# samplehold.net
KiCad netlist of a schematic drawn in EAGLE
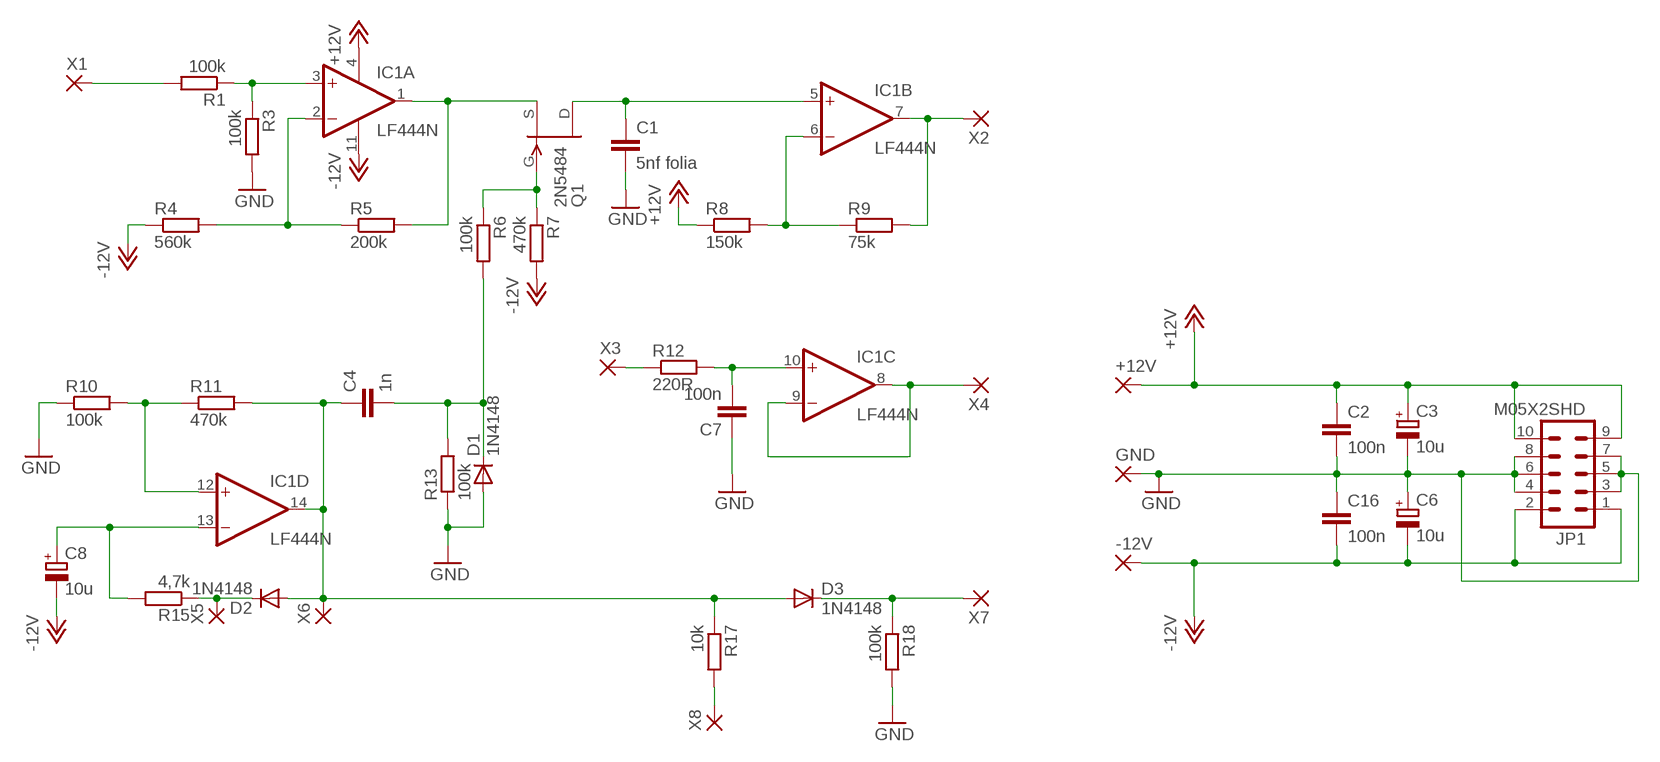
[diagram p0: schematic, sheet 1]
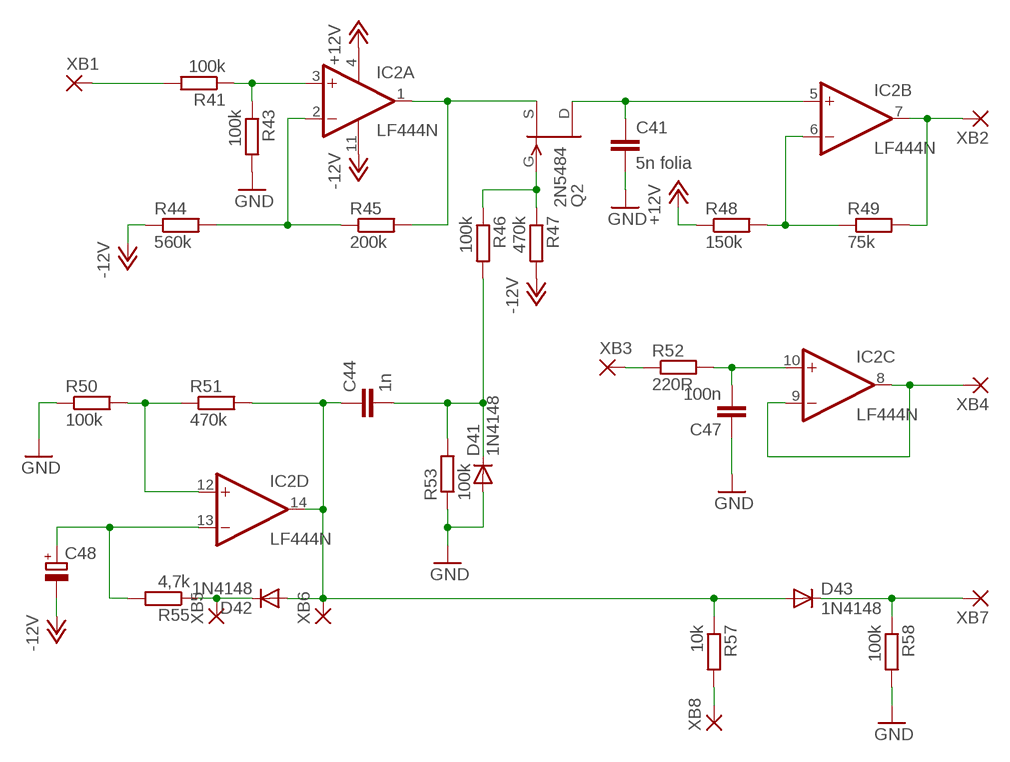
[diagram p1: schematic, sheet 2]

(export (version "E")
  (design (tool "Eeschema 10.0.6"))
  (components
    (comp (ref "+12V")
      (value "2,54/1,0")
      (footprint "eagle-import:2,54_1,0")
      (libsource (lib "eagle-import") (part "2,54/1,0"))
    )
    (comp (ref "-12V")
      (value "2,54/1,0")
      (footprint "eagle-import:2,54_1,0")
      (libsource (lib "eagle-import") (part "2,54/1,0"))
    )
    (comp (ref "C1")
      (value "5nf folia")
      (footprint "eagle-import:C050-035X075")
      (libsource (lib "eagle-import") (part "C-EU050-035X075"))
    )
    (comp (ref "C2")
      (value "100n")
      (footprint "eagle-import:C050-035X075")
      (libsource (lib "eagle-import") (part "C-EU050-035X075"))
    )
    (comp (ref "C3")
      (value "10u")
      (footprint "eagle-import:E3,5-8")
      (libsource (lib "eagle-import") (part "CPOL-EUE3.5-8"))
    )
    (comp (ref "C4")
      (value "1n")
      (footprint "eagle-import:C050-035X075")
      (libsource (lib "eagle-import") (part "C-EU050-035X075"))
    )
    (comp (ref "C6")
      (value "10u")
      (footprint "eagle-import:E3,5-8")
      (libsource (lib "eagle-import") (part "CPOL-EUE3.5-8"))
    )
    (comp (ref "C7")
      (value "100n")
      (footprint "eagle-import:C050-035X075")
      (libsource (lib "eagle-import") (part "C-EU050-035X075"))
    )
    (comp (ref "C8")
      (value "10u")
      (footprint "eagle-import:E2,5-7")
      (libsource (lib "eagle-import") (part "CPOL-EUE2.5-7"))
    )
    (comp (ref "C16")
      (value "100n")
      (footprint "eagle-import:C050-035X075")
      (libsource (lib "eagle-import") (part "C-EU050-035X075"))
    )
    (comp (ref "D1")
      (value "1N4148")
      (footprint "eagle-import:DO35-7")
      (libsource (lib "eagle-import") (part "1N4148DO35-7"))
    )
    (comp (ref "D2")
      (value "1N4148")
      (footprint "eagle-import:DO35-7")
      (libsource (lib "eagle-import") (part "1N4148DO35-7"))
    )
    (comp (ref "D3")
      (value "1N4148")
      (footprint "eagle-import:DO35-7")
      (libsource (lib "eagle-import") (part "1N4148DO35-7"))
    )
    (comp (ref "GND")
      (value "2,54/1,0")
      (footprint "eagle-import:2,54_1,0")
      (libsource (lib "eagle-import") (part "2,54/1,0"))
    )
    (comp (ref "IC1")
      (value "LF444N")
      (footprint "eagle-import:DIL14")
      (libsource (lib "eagle-import") (part "LF444N"))
    )
    (comp (ref "JP1")
      (value "M05X2SHD")
      (footprint "eagle-import:2X5-SHROUDED")
      (libsource (lib "eagle-import") (part "M05X2SHD"))
    )
    (comp (ref "Q1")
      (value "2N5484")
      (footprint "eagle-import:TO92-")
      (libsource (lib "eagle-import") (part "?5482N4"))
    )
    (comp (ref "R1")
      (value "100k")
      (footprint "eagle-import:0309_10")
      (libsource (lib "eagle-import") (part "R-EU_0309/10"))
    )
    (comp (ref "R3")
      (value "100k")
      (footprint "eagle-import:0309_10")
      (libsource (lib "eagle-import") (part "R-EU_0309/10"))
    )
    (comp (ref "R4")
      (value "560k")
      (footprint "eagle-import:0309_10")
      (libsource (lib "eagle-import") (part "R-EU_0309/10"))
    )
    (comp (ref "R5")
      (value "200k")
      (footprint "eagle-import:0309_10")
      (libsource (lib "eagle-import") (part "R-EU_0309/10"))
    )
    (comp (ref "R6")
      (value "100k")
      (footprint "eagle-import:0309_10")
      (libsource (lib "eagle-import") (part "R-EU_0309/10"))
    )
    (comp (ref "R7")
      (value "470k")
      (footprint "eagle-import:0309_10")
      (libsource (lib "eagle-import") (part "R-EU_0309/10"))
    )
    (comp (ref "R8")
      (value "150k")
      (footprint "eagle-import:0309_10")
      (libsource (lib "eagle-import") (part "R-EU_0309/10"))
    )
    (comp (ref "R9")
      (value "75k")
      (footprint "eagle-import:0309_10")
      (libsource (lib "eagle-import") (part "R-EU_0309/10"))
    )
    (comp (ref "R10")
      (value "100k")
      (footprint "eagle-import:0309_10")
      (libsource (lib "eagle-import") (part "R-EU_0309/10"))
    )
    (comp (ref "R11")
      (value "470k")
      (footprint "eagle-import:0309_10")
      (libsource (lib "eagle-import") (part "R-EU_0309/10"))
    )
    (comp (ref "R12")
      (value "220R")
      (footprint "eagle-import:0309_10")
      (libsource (lib "eagle-import") (part "R-EU_0309/10"))
    )
    (comp (ref "R13")
      (value "100k")
      (footprint "eagle-import:0309_10")
      (libsource (lib "eagle-import") (part "R-EU_0309/10"))
    )
    (comp (ref "R15")
      (value "4,7k")
      (footprint "eagle-import:0309_10")
      (libsource (lib "eagle-import") (part "R-EU_0309/10"))
    )
    (comp (ref "R17")
      (value "10k")
      (footprint "eagle-import:0309_10")
      (libsource (lib "eagle-import") (part "R-EU_0309/10"))
    )
    (comp (ref "R18")
      (value "100k")
      (footprint "eagle-import:0309_10")
      (libsource (lib "eagle-import") (part "R-EU_0309/10"))
    )
    (comp (ref "X1")
      (value "2,54/1,0")
      (footprint "eagle-import:2,54_1,0")
      (libsource (lib "eagle-import") (part "2,54/1,0"))
    )
    (comp (ref "X2")
      (value "2,54/1,0")
      (footprint "eagle-import:2,54_1,0")
      (libsource (lib "eagle-import") (part "2,54/1,0"))
    )
    (comp (ref "X3")
      (value "2,54/1,0")
      (footprint "eagle-import:2,54_1,0")
      (libsource (lib "eagle-import") (part "2,54/1,0"))
    )
    (comp (ref "X4")
      (value "2,54/1,0")
      (footprint "eagle-import:2,54_1,0")
      (libsource (lib "eagle-import") (part "2,54/1,0"))
    )
    (comp (ref "X5")
      (value "2,54/1,0")
      (footprint "eagle-import:2,54_1,0")
      (libsource (lib "eagle-import") (part "2,54/1,0"))
    )
    (comp (ref "X6")
      (value "2,54/1,0")
      (footprint "eagle-import:2,54_1,0")
      (libsource (lib "eagle-import") (part "2,54/1,0"))
    )
    (comp (ref "X7")
      (value "2,54/1,0")
      (footprint "eagle-import:2,54_1,0")
      (libsource (lib "eagle-import") (part "2,54/1,0"))
    )
    (comp (ref "X8")
      (value "2,54/1,0")
      (footprint "eagle-import:2,54_1,0")
      (libsource (lib "eagle-import") (part "2,54/1,0"))
    )
    (comp (ref "C41")
      (value "5n folia")
      (footprint "eagle-import:C050-035X075")
      (libsource (lib "eagle-import") (part "C-EU050-035X075"))
    )
    (comp (ref "C44")
      (value "1n")
      (footprint "eagle-import:C050-035X075")
      (libsource (lib "eagle-import") (part "C-EU050-035X075"))
    )
    (comp (ref "C47")
      (value "100n")
      (footprint "eagle-import:C050-035X075")
      (libsource (lib "eagle-import") (part "C-EU050-035X075"))
    )
    (comp (ref "C48")
      (value "CPOL-EUE2.5-7")
      (footprint "eagle-import:E2,5-7")
      (libsource (lib "eagle-import") (part "CPOL-EUE2.5-7"))
    )
    (comp (ref "D41")
      (value "1N4148")
      (footprint "eagle-import:DO35-7")
      (libsource (lib "eagle-import") (part "1N4148DO35-7"))
    )
    (comp (ref "D42")
      (value "1N4148")
      (footprint "eagle-import:DO35-7")
      (libsource (lib "eagle-import") (part "1N4148DO35-7"))
    )
    (comp (ref "D43")
      (value "1N4148")
      (footprint "eagle-import:DO35-7")
      (libsource (lib "eagle-import") (part "1N4148DO35-7"))
    )
    (comp (ref "IC2")
      (value "LF444N")
      (footprint "eagle-import:DIL14")
      (libsource (lib "eagle-import") (part "LF444N"))
    )
    (comp (ref "Q2")
      (value "2N5484")
      (footprint "eagle-import:TO92-")
      (libsource (lib "eagle-import") (part "?5482N4"))
    )
    (comp (ref "R41")
      (value "100k")
      (footprint "eagle-import:0309_10")
      (libsource (lib "eagle-import") (part "R-EU_0309/10"))
    )
    (comp (ref "R43")
      (value "100k")
      (footprint "eagle-import:0309_10")
      (libsource (lib "eagle-import") (part "R-EU_0309/10"))
    )
    (comp (ref "R44")
      (value "560k")
      (footprint "eagle-import:0309_10")
      (libsource (lib "eagle-import") (part "R-EU_0309/10"))
    )
    (comp (ref "R45")
      (value "200k")
      (footprint "eagle-import:0309_10")
      (libsource (lib "eagle-import") (part "R-EU_0309/10"))
    )
    (comp (ref "R46")
      (value "100k")
      (footprint "eagle-import:0309_10")
      (libsource (lib "eagle-import") (part "R-EU_0309/10"))
    )
    (comp (ref "R47")
      (value "470k")
      (footprint "eagle-import:0309_10")
      (libsource (lib "eagle-import") (part "R-EU_0309/10"))
    )
    (comp (ref "R48")
      (value "150k")
      (footprint "eagle-import:0309_10")
      (libsource (lib "eagle-import") (part "R-EU_0309/10"))
    )
    (comp (ref "R49")
      (value "75k")
      (footprint "eagle-import:0309_10")
      (libsource (lib "eagle-import") (part "R-EU_0309/10"))
    )
    (comp (ref "R50")
      (value "100k")
      (footprint "eagle-import:0309_10")
      (libsource (lib "eagle-import") (part "R-EU_0309/10"))
    )
    (comp (ref "R51")
      (value "470k")
      (footprint "eagle-import:0309_10")
      (libsource (lib "eagle-import") (part "R-EU_0309/10"))
    )
    (comp (ref "R52")
      (value "220R")
      (footprint "eagle-import:0309_10")
      (libsource (lib "eagle-import") (part "R-EU_0309/10"))
    )
    (comp (ref "R53")
      (value "100k")
      (footprint "eagle-import:0309_10")
      (libsource (lib "eagle-import") (part "R-EU_0309/10"))
    )
    (comp (ref "R55")
      (value "4,7k")
      (footprint "eagle-import:0309_10")
      (libsource (lib "eagle-import") (part "R-EU_0309/10"))
    )
    (comp (ref "R57")
      (value "10k")
      (footprint "eagle-import:0309_10")
      (libsource (lib "eagle-import") (part "R-EU_0309/10"))
    )
    (comp (ref "R58")
      (value "100k")
      (footprint "eagle-import:0309_10")
      (libsource (lib "eagle-import") (part "R-EU_0309/10"))
    )
    (comp (ref "XB1")
      (value "2,54/1,0")
      (footprint "eagle-import:2,54_1,0")
      (libsource (lib "eagle-import") (part "2,54/1,0"))
    )
    (comp (ref "XB2")
      (value "2,54/1,0")
      (footprint "eagle-import:2,54_1,0")
      (libsource (lib "eagle-import") (part "2,54/1,0"))
    )
    (comp (ref "XB3")
      (value "2,54/1,0")
      (footprint "eagle-import:2,54_1,0")
      (libsource (lib "eagle-import") (part "2,54/1,0"))
    )
    (comp (ref "XB4")
      (value "2,54/1,0")
      (footprint "eagle-import:2,54_1,0")
      (libsource (lib "eagle-import") (part "2,54/1,0"))
    )
    (comp (ref "XB5")
      (value "2,54/1,0")
      (footprint "eagle-import:2,54_1,0")
      (libsource (lib "eagle-import") (part "2,54/1,0"))
    )
    (comp (ref "XB6")
      (value "2,54/1,0")
      (footprint "eagle-import:2,54_1,0")
      (libsource (lib "eagle-import") (part "2,54/1,0"))
    )
    (comp (ref "XB7")
      (value "2,54/1,0")
      (footprint "eagle-import:2,54_1,0")
      (libsource (lib "eagle-import") (part "2,54/1,0"))
    )
    (comp (ref "XB8")
      (value "2,54/1,0")
      (footprint "eagle-import:2,54_1,0")
      (libsource (lib "eagle-import") (part "2,54/1,0"))
    )
  )
  (nets
    (net (code "1") (name "+12V") (class "Default")
      (node (ref "+12V") (pin "1") (pinfunction "P_1") (pintype "passive"))
      (node (ref "C2") (pin "1") (pinfunction "1_1") (pintype "passive"))
      (node (ref "C3") (pin "+") (pinfunction "+_+") (pintype "passive"))
      (node (ref "IC1") (pin "4") (pinfunction "V+_4") (pintype "power_in"))
      (node (ref "IC2") (pin "4") (pinfunction "V+_4") (pintype "power_in"))
      (node (ref "JP1") (pin "10") (pinfunction "10_10") (pintype "passive"))
      (node (ref "JP1") (pin "9") (pinfunction "9_9") (pintype "passive"))
      (node (ref "R48") (pin "1") (pinfunction "1_1") (pintype "passive"))
      (node (ref "R8") (pin "1") (pinfunction "1_1") (pintype "passive"))
    )
    (net (code "2") (name "-12V") (class "Default")
      (node (ref "-12V") (pin "1") (pinfunction "P_1") (pintype "passive"))
      (node (ref "C16") (pin "2") (pinfunction "2_2") (pintype "passive"))
      (node (ref "C48") (pin "-") (pinfunction "-_-") (pintype "passive"))
      (node (ref "C6") (pin "-") (pinfunction "-_-") (pintype "passive"))
      (node (ref "C8") (pin "-") (pinfunction "-_-") (pintype "passive"))
      (node (ref "IC1") (pin "11") (pinfunction "V-_11") (pintype "power_in"))
      (node (ref "IC2") (pin "11") (pinfunction "V-_11") (pintype "power_in"))
      (node (ref "JP1") (pin "1") (pinfunction "1_1") (pintype "passive"))
      (node (ref "JP1") (pin "2") (pinfunction "2_2") (pintype "passive"))
      (node (ref "R4") (pin "1") (pinfunction "1_1") (pintype "passive"))
      (node (ref "R44") (pin "1") (pinfunction "1_1") (pintype "passive"))
      (node (ref "R47") (pin "2") (pinfunction "2_2") (pintype "passive"))
      (node (ref "R7") (pin "2") (pinfunction "2_2") (pintype "passive"))
    )
    (net (code "3") (name "GND") (class "Default")
      (node (ref "C1") (pin "2") (pinfunction "2_2") (pintype "passive"))
      (node (ref "C16") (pin "1") (pinfunction "1_1") (pintype "passive"))
      (node (ref "C2") (pin "2") (pinfunction "2_2") (pintype "passive"))
      (node (ref "C3") (pin "-") (pinfunction "-_-") (pintype "passive"))
      (node (ref "C41") (pin "2") (pinfunction "2_2") (pintype "passive"))
      (node (ref "C47") (pin "1") (pinfunction "1_1") (pintype "passive"))
      (node (ref "C6") (pin "+") (pinfunction "+_+") (pintype "passive"))
      (node (ref "C7") (pin "1") (pinfunction "1_1") (pintype "passive"))
      (node (ref "D1") (pin "A") (pinfunction "A_A") (pintype "passive"))
      (node (ref "D41") (pin "A") (pinfunction "A_A") (pintype "passive"))
      (node (ref "GND") (pin "1") (pinfunction "P_1") (pintype "passive"))
      (node (ref "JP1") (pin "3") (pinfunction "3_3") (pintype "passive"))
      (node (ref "JP1") (pin "4") (pinfunction "4_4") (pintype "passive"))
      (node (ref "JP1") (pin "5") (pinfunction "5_5") (pintype "passive"))
      (node (ref "JP1") (pin "6") (pinfunction "6_6") (pintype "passive"))
      (node (ref "JP1") (pin "7") (pinfunction "7_7") (pintype "passive"))
      (node (ref "JP1") (pin "8") (pinfunction "8_8") (pintype "passive"))
      (node (ref "R10") (pin "1") (pinfunction "1_1") (pintype "passive"))
      (node (ref "R13") (pin "1") (pinfunction "1_1") (pintype "passive"))
      (node (ref "R18") (pin "2") (pinfunction "2_2") (pintype "passive"))
      (node (ref "R3") (pin "2") (pinfunction "2_2") (pintype "passive"))
      (node (ref "R43") (pin "2") (pinfunction "2_2") (pintype "passive"))
      (node (ref "R50") (pin "1") (pinfunction "1_1") (pintype "passive"))
      (node (ref "R53") (pin "1") (pinfunction "1_1") (pintype "passive"))
      (node (ref "R58") (pin "2") (pinfunction "2_2") (pintype "passive"))
    )
    (net (code "4") (name "Net-(C4-Pad2)") (class "Default")
      (node (ref "C4") (pin "2") (pinfunction "2_2") (pintype "passive"))
      (node (ref "D1") (pin "C") (pinfunction "C_C") (pintype "passive"))
      (node (ref "R13") (pin "2") (pinfunction "2_2") (pintype "passive"))
      (node (ref "R6") (pin "2") (pinfunction "2_2") (pintype "passive"))
    )
    (net (code "5") (name "Net-(C44-Pad2)") (class "Default")
      (node (ref "C44") (pin "2") (pinfunction "2_2") (pintype "passive"))
      (node (ref "D41") (pin "C") (pinfunction "C_C") (pintype "passive"))
      (node (ref "R46") (pin "2") (pinfunction "2_2") (pintype "passive"))
      (node (ref "R53") (pin "2") (pinfunction "2_2") (pintype "passive"))
    )
    (net (code "6") (name "Net-(IC1A-+IN)") (class "Default")
      (node (ref "IC1") (pin "3") (pinfunction "+IN_3") (pintype "input"))
      (node (ref "R1") (pin "1") (pinfunction "1_1") (pintype "passive"))
      (node (ref "R3") (pin "1") (pinfunction "1_1") (pintype "passive"))
    )
    (net (code "7") (name "Net-(IC1A--IN)") (class "Default")
      (node (ref "IC1") (pin "2") (pinfunction "-IN_2") (pintype "input"))
      (node (ref "R4") (pin "2") (pinfunction "2_2") (pintype "passive"))
      (node (ref "R5") (pin "1") (pinfunction "1_1") (pintype "passive"))
    )
    (net (code "8") (name "Net-(IC1A-OUT)") (class "Default")
      (node (ref "IC1") (pin "1") (pinfunction "OUT_1") (pintype "output"))
      (node (ref "Q1") (pin "2") (pinfunction "S_2") (pintype "passive"))
      (node (ref "R5") (pin "2") (pinfunction "2_2") (pintype "passive"))
    )
    (net (code "9") (name "Net-(IC1B-+IN)") (class "Default")
      (node (ref "C1") (pin "1") (pinfunction "1_1") (pintype "passive"))
      (node (ref "IC1") (pin "5") (pinfunction "+IN_5") (pintype "input"))
      (node (ref "Q1") (pin "3") (pinfunction "D_3") (pintype "passive"))
    )
    (net (code "10") (name "Net-(IC1B--IN)") (class "Default")
      (node (ref "IC1") (pin "6") (pinfunction "-IN_6") (pintype "input"))
      (node (ref "R8") (pin "2") (pinfunction "2_2") (pintype "passive"))
      (node (ref "R9") (pin "1") (pinfunction "1_1") (pintype "passive"))
    )
    (net (code "11") (name "Net-(IC1B-OUT)") (class "Default")
      (node (ref "IC1") (pin "7") (pinfunction "OUT_7") (pintype "output"))
      (node (ref "R9") (pin "2") (pinfunction "2_2") (pintype "passive"))
      (node (ref "X2") (pin "1") (pinfunction "P_1") (pintype "passive"))
    )
    (net (code "12") (name "Net-(IC1C-+IN)") (class "Default")
      (node (ref "C7") (pin "2") (pinfunction "2_2") (pintype "passive"))
      (node (ref "IC1") (pin "10") (pinfunction "+IN_10") (pintype "input"))
      (node (ref "R12") (pin "2") (pinfunction "2_2") (pintype "passive"))
    )
    (net (code "13") (name "Net-(IC1C--IN)") (class "Default")
      (node (ref "IC1") (pin "8") (pinfunction "OUT_8") (pintype "output"))
      (node (ref "IC1") (pin "9") (pinfunction "-IN_9") (pintype "input"))
      (node (ref "X4") (pin "1") (pinfunction "P_1") (pintype "passive"))
    )
    (net (code "14") (name "Net-(IC1D-+IN)") (class "Default")
      (node (ref "IC1") (pin "12") (pinfunction "+IN_12") (pintype "input"))
      (node (ref "R10") (pin "2") (pinfunction "2_2") (pintype "passive"))
      (node (ref "R11") (pin "1") (pinfunction "1_1") (pintype "passive"))
    )
    (net (code "15") (name "Net-(IC1D--IN)") (class "Default")
      (node (ref "C8") (pin "+") (pinfunction "+_+") (pintype "passive"))
      (node (ref "IC1") (pin "13") (pinfunction "-IN_13") (pintype "input"))
      (node (ref "R15") (pin "2") (pinfunction "2_2") (pintype "passive"))
    )
    (net (code "16") (name "Net-(IC1D-OUT)") (class "Default")
      (node (ref "C4") (pin "1") (pinfunction "1_1") (pintype "passive"))
      (node (ref "D2") (pin "A") (pinfunction "A_A") (pintype "passive"))
      (node (ref "D3") (pin "A") (pinfunction "A_A") (pintype "passive"))
      (node (ref "IC1") (pin "14") (pinfunction "OUT_14") (pintype "output"))
      (node (ref "R11") (pin "2") (pinfunction "2_2") (pintype "passive"))
      (node (ref "R17") (pin "1") (pinfunction "1_1") (pintype "passive"))
      (node (ref "X6") (pin "1") (pinfunction "P_1") (pintype "passive"))
    )
    (net (code "17") (name "Net-(IC2A-+IN)") (class "Default")
      (node (ref "IC2") (pin "3") (pinfunction "+IN_3") (pintype "input"))
      (node (ref "R41") (pin "1") (pinfunction "1_1") (pintype "passive"))
      (node (ref "R43") (pin "1") (pinfunction "1_1") (pintype "passive"))
    )
    (net (code "18") (name "Net-(IC2A--IN)") (class "Default")
      (node (ref "IC2") (pin "2") (pinfunction "-IN_2") (pintype "input"))
      (node (ref "R44") (pin "2") (pinfunction "2_2") (pintype "passive"))
      (node (ref "R45") (pin "1") (pinfunction "1_1") (pintype "passive"))
    )
    (net (code "19") (name "Net-(IC2A-OUT)") (class "Default")
      (node (ref "IC2") (pin "1") (pinfunction "OUT_1") (pintype "output"))
      (node (ref "Q2") (pin "2") (pinfunction "S_2") (pintype "passive"))
      (node (ref "R45") (pin "2") (pinfunction "2_2") (pintype "passive"))
    )
    (net (code "20") (name "Net-(IC2B-+IN)") (class "Default")
      (node (ref "C41") (pin "1") (pinfunction "1_1") (pintype "passive"))
      (node (ref "IC2") (pin "5") (pinfunction "+IN_5") (pintype "input"))
      (node (ref "Q2") (pin "3") (pinfunction "D_3") (pintype "passive"))
    )
    (net (code "21") (name "Net-(IC2B--IN)") (class "Default")
      (node (ref "IC2") (pin "6") (pinfunction "-IN_6") (pintype "input"))
      (node (ref "R48") (pin "2") (pinfunction "2_2") (pintype "passive"))
      (node (ref "R49") (pin "1") (pinfunction "1_1") (pintype "passive"))
    )
    (net (code "22") (name "Net-(IC2B-OUT)") (class "Default")
      (node (ref "IC2") (pin "7") (pinfunction "OUT_7") (pintype "output"))
      (node (ref "R49") (pin "2") (pinfunction "2_2") (pintype "passive"))
      (node (ref "XB2") (pin "1") (pinfunction "P_1") (pintype "passive"))
    )
    (net (code "23") (name "Net-(IC2C-+IN)") (class "Default")
      (node (ref "C47") (pin "2") (pinfunction "2_2") (pintype "passive"))
      (node (ref "IC2") (pin "10") (pinfunction "+IN_10") (pintype "input"))
      (node (ref "R52") (pin "2") (pinfunction "2_2") (pintype "passive"))
    )
    (net (code "24") (name "Net-(IC2C--IN)") (class "Default")
      (node (ref "IC2") (pin "8") (pinfunction "OUT_8") (pintype "output"))
      (node (ref "IC2") (pin "9") (pinfunction "-IN_9") (pintype "input"))
      (node (ref "XB4") (pin "1") (pinfunction "P_1") (pintype "passive"))
    )
    (net (code "25") (name "Net-(IC2D-+IN)") (class "Default")
      (node (ref "IC2") (pin "12") (pinfunction "+IN_12") (pintype "input"))
      (node (ref "R50") (pin "2") (pinfunction "2_2") (pintype "passive"))
      (node (ref "R51") (pin "1") (pinfunction "1_1") (pintype "passive"))
    )
    (net (code "26") (name "Net-(IC2D--IN)") (class "Default")
      (node (ref "C48") (pin "+") (pinfunction "+_+") (pintype "passive"))
      (node (ref "IC2") (pin "13") (pinfunction "-IN_13") (pintype "input"))
      (node (ref "R55") (pin "2") (pinfunction "2_2") (pintype "passive"))
    )
    (net (code "27") (name "Net-(IC2D-OUT)") (class "Default")
      (node (ref "C44") (pin "1") (pinfunction "1_1") (pintype "passive"))
      (node (ref "D42") (pin "A") (pinfunction "A_A") (pintype "passive"))
      (node (ref "D43") (pin "A") (pinfunction "A_A") (pintype "passive"))
      (node (ref "IC2") (pin "14") (pinfunction "OUT_14") (pintype "output"))
      (node (ref "R51") (pin "2") (pinfunction "2_2") (pintype "passive"))
      (node (ref "R57") (pin "1") (pinfunction "1_1") (pintype "passive"))
      (node (ref "XB6") (pin "1") (pinfunction "P_1") (pintype "passive"))
    )
    (net (code "28") (name "Net-(Q1-G)") (class "Default")
      (node (ref "Q1") (pin "1") (pinfunction "G_1") (pintype "passive"))
      (node (ref "R6") (pin "1") (pinfunction "1_1") (pintype "passive"))
      (node (ref "R7") (pin "1") (pinfunction "1_1") (pintype "passive"))
    )
    (net (code "29") (name "Net-(Q2-G)") (class "Default")
      (node (ref "Q2") (pin "1") (pinfunction "G_1") (pintype "passive"))
      (node (ref "R46") (pin "1") (pinfunction "1_1") (pintype "passive"))
      (node (ref "R47") (pin "1") (pinfunction "1_1") (pintype "passive"))
    )
    (net (code "30") (name "Net-(X1-P)") (class "Default")
      (node (ref "R1") (pin "2") (pinfunction "2_2") (pintype "passive"))
      (node (ref "X1") (pin "1") (pinfunction "P_1") (pintype "passive"))
    )
    (net (code "31") (name "Net-(X3-P)") (class "Default")
      (node (ref "R12") (pin "1") (pinfunction "1_1") (pintype "passive"))
      (node (ref "X3") (pin "1") (pinfunction "P_1") (pintype "passive"))
    )
    (net (code "32") (name "Net-(X5-P)") (class "Default")
      (node (ref "D2") (pin "C") (pinfunction "C_C") (pintype "passive"))
      (node (ref "R15") (pin "1") (pinfunction "1_1") (pintype "passive"))
      (node (ref "X5") (pin "1") (pinfunction "P_1") (pintype "passive"))
    )
    (net (code "33") (name "Net-(X7-P)") (class "Default")
      (node (ref "D3") (pin "C") (pinfunction "C_C") (pintype "passive"))
      (node (ref "R18") (pin "1") (pinfunction "1_1") (pintype "passive"))
      (node (ref "X7") (pin "1") (pinfunction "P_1") (pintype "passive"))
    )
    (net (code "34") (name "Net-(X8-P)") (class "Default")
      (node (ref "R17") (pin "2") (pinfunction "2_2") (pintype "passive"))
      (node (ref "X8") (pin "1") (pinfunction "P_1") (pintype "passive"))
    )
    (net (code "35") (name "Net-(XB1-P)") (class "Default")
      (node (ref "R41") (pin "2") (pinfunction "2_2") (pintype "passive"))
      (node (ref "XB1") (pin "1") (pinfunction "P_1") (pintype "passive"))
    )
    (net (code "36") (name "Net-(XB3-P)") (class "Default")
      (node (ref "R52") (pin "1") (pinfunction "1_1") (pintype "passive"))
      (node (ref "XB3") (pin "1") (pinfunction "P_1") (pintype "passive"))
    )
    (net (code "37") (name "Net-(XB5-P)") (class "Default")
      (node (ref "D42") (pin "C") (pinfunction "C_C") (pintype "passive"))
      (node (ref "R55") (pin "1") (pinfunction "1_1") (pintype "passive"))
      (node (ref "XB5") (pin "1") (pinfunction "P_1") (pintype "passive"))
    )
    (net (code "38") (name "Net-(XB7-P)") (class "Default")
      (node (ref "D43") (pin "C") (pinfunction "C_C") (pintype "passive"))
      (node (ref "R58") (pin "1") (pinfunction "1_1") (pintype "passive"))
      (node (ref "XB7") (pin "1") (pinfunction "P_1") (pintype "passive"))
    )
    (net (code "39") (name "Net-(XB8-P)") (class "Default")
      (node (ref "R57") (pin "2") (pinfunction "2_2") (pintype "passive"))
      (node (ref "XB8") (pin "1") (pinfunction "P_1") (pintype "passive"))
    )
  )
)
